# CHRT.net
KiCad netlist of a schematic drawn in Altium Designer
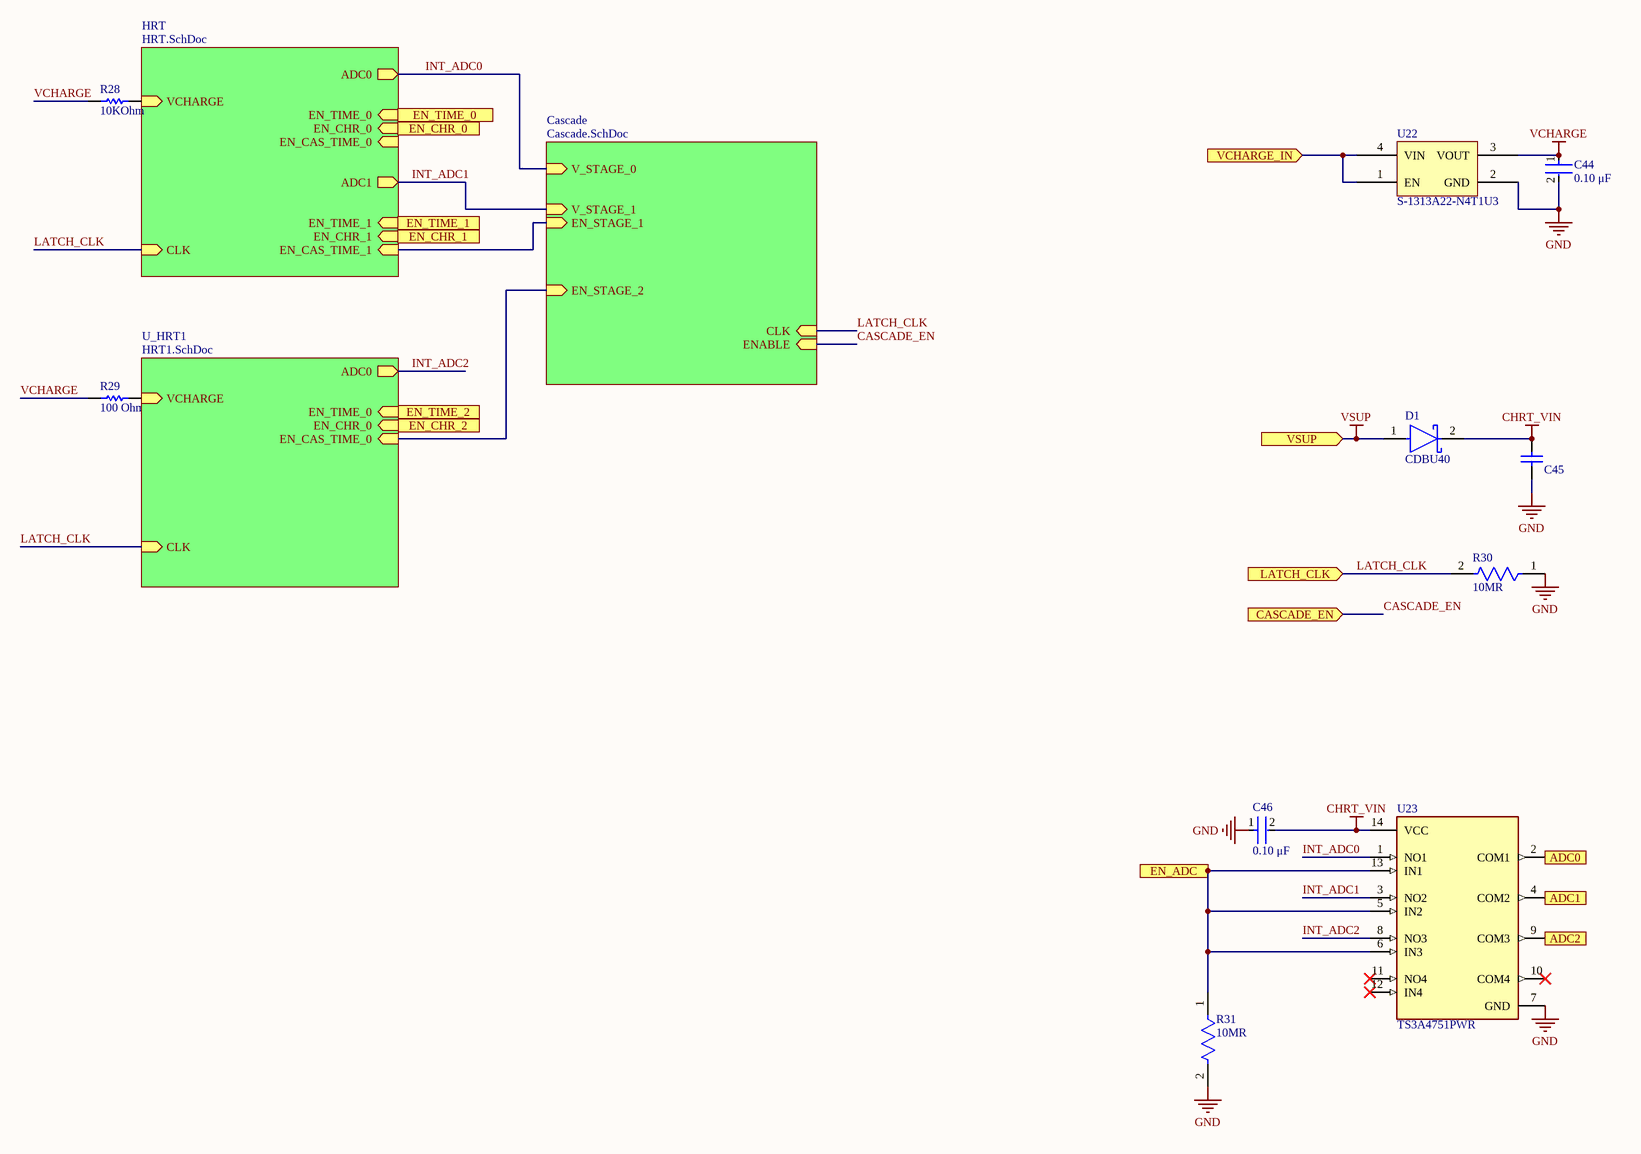
[diagram p0: CHRT.SchDoc]

(export (version "E")
  (design (tool "Eeschema 10.0.6"))
  (components
    (comp (ref "C44")
      (value "C0402C104K8PACTU")
      (footprint "FP-C0402-BB-MFG")
      (description "CAP CER 0.1UF 10V X5R 0402")
      (fields
        (field (name "CAPACITANCE") "0.10 μF")
        (field (name "MANUFACTURER") "Kemet")
        (field (name "TOLERANCE") "0.1")
      )
      (libsource (lib "Altium Content Vault") (part "b4654b650e69147ec39a6b967a45e02"))
    )
    (comp (ref "C45")
      (value "ZRB15XR61A106ME01D")
      (footprint "CAPC1005X55X25NL05T10")
      (fields (field (name "MANUFACTURER") "Murata") (field (name "PART NUMBER") "GRM155R60G106ME44D"))
      (libsource (lib "Altium Content Vault") (part "CAP"))
    )
    (comp (ref "C46")
      (value "C0402C104K8PACTU")
      (footprint "FP-C0402-BB-MFG")
      (description "CAP CER 0.1UF 10V X5R 0402")
      (fields
        (field (name "CAPACITANCE") "0.10 μF")
        (field (name "MANUFACTURER") "Kemet")
        (field (name "TOLERANCE") "0.1")
      )
      (libsource (lib "Altium Content Vault") (part "b4654b650e69147ec39a6b967a45e02"))
    )
    (comp (ref "D1")
      (value "CDBU40")
      (footprint "FP-S8-V-3880_02-001-MFG")
      (description "DIODE SCHOTTKY 40V 120MA SOD523")
      (fields
        (field (name "OCTOPART") "https://octopart.com/bas40-02v-v-g-08-vishay-44351221")
        (field (name "MANUFACTURER") "Vishay")
      )
      (libsource (lib "Altium Content Vault") (part "360ad2f4ac25a952324d13796385471"))
    )
    (comp (ref "R28")
      (value "RMCF0402FT10K0")
      (footprint "RESC1005X40X25LL05T05")
      (description "Chip Resistor, 10 KOhm, +/- 1%, 0.1 W, -55 to 155 degC, 0402 (1005 Metric), RoHS, Tape and Reel")
      (fields
        (field (name "RESISTANCE") "10KOhm")
        (field (name "TOLERANCE") "1%")
        (field (name "MANUFACTURER") "Panasonic")
      )
      (libsource (lib "Altium Content Vault") (part "RES-2"))
    )
    (comp (ref "R29")
      (value "ERJ-2RKF1000X")
      (footprint "RESC1005X40X25LL05T05")
      (description "Chip Resistor, 100 Ohm, +/- 1%, 100 mW, -55 to 155 degC, 0402 (1005 Metric), RoHS, Tape and Reel")
      (fields
        (field (name "MANUFACTURER") "Basic Passives")
        (field (name "TOLERANCE") "1%")
        (field (name "RESISTANCE") "100 Ohm")
      )
      (libsource (lib "Altium Content Vault") (part "RES-2"))
    )
    (comp (ref "R30")
      (value "CRCW040210M0JNED")
      (footprint "FP-CRCW0402-e3-IPC_C")
      (description "RES Thick Film, 10MΩ, 5%, 0.063W, 200ppm/°C, 0402")
      (fields (field (name "TOLERANCE") "5%") (field (name "RESISTANCE") "10MR"))
      (libsource (lib "Altium Content Vault") (part "1029c3af85768c4190bb7ad29bc67b5"))
    )
    (comp (ref "R31")
      (value "CRCW040210M0JNED")
      (footprint "FP-CRCW0402-e3-IPC_C")
      (description "RES Thick Film, 10MΩ, 5%, 0.063W, 200ppm/°C, 0402")
      (fields (field (name "TOLERANCE") "5%") (field (name "RESISTANCE") "10MR"))
      (libsource (lib "Altium Content Vault") (part "1029c3af85768c4190bb7ad29bc67b5"))
    )
    (comp (ref "U22")
      (value "S-1313A22-N4T1U3")
      (footprint "SOT130P210X110-4N")
      (libsource (lib "Integrated_Library1") (part "S-1313A22-N4T1U3"))
    )
    (comp (ref "U23")
      (value "TS3A4751PWR")
      (footprint "FP-PW0014A-IPC_C")
      (description "IC SWITCH QUAD SPST 14TSSOP")
      (libsource (lib "Altium Content Vault") (part "75fdcfb842d41a92b92a478e82e68ae"))
    )
  )
  (nets
    (net (code "1") (name "/ADC0") (class "Default")
      (node (ref "U23") (pin "2") (pinfunction "COM1_2") (pintype "output"))
    )
    (net (code "2") (name "/ADC1") (class "Default")
      (node (ref "U23") (pin "4") (pinfunction "COM2_4") (pintype "output"))
    )
    (net (code "3") (name "/ADC2") (class "Default")
      (node (ref "U23") (pin "9") (pinfunction "COM3_9") (pintype "output"))
    )
    (net (code "5") (name "/EN_ADC") (class "Default")
      (node (ref "R31") (pin "1") (pinfunction "1_1") (pintype "passive"))
      (node (ref "U23") (pin "13") (pinfunction "IN1_13") (pintype "input"))
      (node (ref "U23") (pin "5") (pinfunction "IN2_5") (pintype "input"))
      (node (ref "U23") (pin "6") (pinfunction "IN3_6") (pintype "input"))
    )
    (net (code "15") (name "/INT_ADC0") (class "Default")
      (node (ref "U23") (pin "1") (pinfunction "NO1_1") (pintype "input"))
    )
    (net (code "16") (name "/INT_ADC1") (class "Default")
      (node (ref "U23") (pin "3") (pinfunction "NO2_3") (pintype "input"))
    )
    (net (code "17") (name "/INT_ADC2") (class "Default")
      (node (ref "U23") (pin "8") (pinfunction "NO3_8") (pintype "input"))
    )
    (net (code "18") (name "/LATCH_CLK") (class "Default")
      (node (ref "R30") (pin "2") (pinfunction "2_2") (pintype "passive"))
    )
    (net (code "19") (name "/VCHARGE_1") (class "Default")
      (node (ref "R29") (pin "2") (pinfunction "2_2") (pintype "passive"))
    )
    (net (code "20") (name "/VCHARGE_2") (class "Default")
      (node (ref "R28") (pin "2") (pinfunction "2_2") (pintype "passive"))
    )
    (net (code "21") (name "/VCHARGE_IN") (class "Default")
      (node (ref "U22") (pin "1") (pinfunction "EN_1") (pintype "passive"))
      (node (ref "U22") (pin "4") (pinfunction "VIN_4") (pintype "passive"))
    )
    (net (code "22") (name "CHRT_VIN") (class "Default")
      (node (ref "C45") (pin "2") (pinfunction "2_2") (pintype "passive"))
      (node (ref "C46") (pin "2") (pinfunction "2_2") (pintype "passive"))
      (node (ref "D1") (pin "2") (pinfunction "C_2") (pintype "passive"))
      (node (ref "U23") (pin "14") (pinfunction "VCC_14") (pintype "power_in"))
    )
    (net (code "23") (name "GND") (class "Default")
      (node (ref "C44") (pin "2") (pinfunction "2_2") (pintype "passive"))
      (node (ref "C45") (pin "1") (pinfunction "1_1") (pintype "passive"))
      (node (ref "C46") (pin "1") (pinfunction "1_1") (pintype "passive"))
      (node (ref "R30") (pin "1") (pinfunction "1_1") (pintype "passive"))
      (node (ref "R31") (pin "2") (pinfunction "2_2") (pintype "passive"))
      (node (ref "U22") (pin "2") (pinfunction "GND_2") (pintype "passive"))
      (node (ref "U23") (pin "7") (pinfunction "GND_7") (pintype "power_in"))
    )
    (net (code "24") (name "VCHARGE") (class "Default")
      (node (ref "C44") (pin "1") (pinfunction "1_1") (pintype "passive"))
      (node (ref "R28") (pin "1") (pinfunction "1_1") (pintype "passive"))
      (node (ref "R29") (pin "1") (pinfunction "1_1") (pintype "passive"))
      (node (ref "U22") (pin "3") (pinfunction "VOUT_3") (pintype "passive"))
    )
    (net (code "25") (name "VSUP") (class "Default")
      (node (ref "D1") (pin "1") (pinfunction "A_1") (pintype "passive"))
    )
    (net (code "26") (name "unconnected-(U23-COM4-Pad10)") (class "Default")
      (node (ref "U23") (pin "10") (pinfunction "COM4_10") (pintype "output+no_connect"))
    )
    (net (code "27") (name "unconnected-(U23-IN4-Pad12)") (class "Default")
      (node (ref "U23") (pin "12") (pinfunction "IN4_12") (pintype "input+no_connect"))
    )
    (net (code "28") (name "unconnected-(U23-NO4-Pad11)") (class "Default")
      (node (ref "U23") (pin "11") (pinfunction "NO4_11") (pintype "input+no_connect"))
    )
  )
)
